# TFT_LCD_ER-TFT018-2.net
KiCad netlist of a schematic drawn in Altium Designer
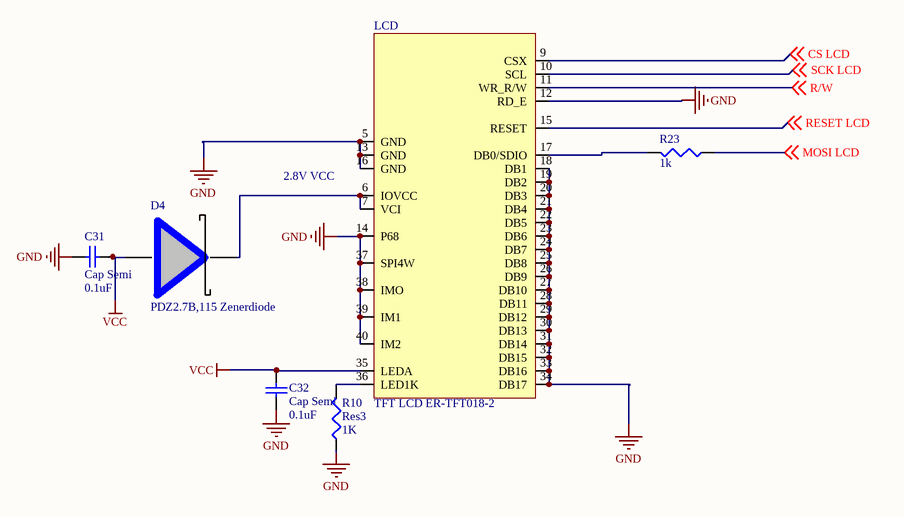
[diagram p0: TFT LCD ER-TFT018-2.SchDoc]

(export (version "E")
  (design (tool "Eeschema 10.0.6"))
  (components
    (comp (ref "C31")
      (value "Cap Semi")
      (footprint "1608[0603]")
      (description "Capacitor (Semiconductor SIM Model)")
      (fields (field (name "ALTIUM_VALUE") "0.1uF") (field (name "PUBLISHER") "Altium Limited"))
      (libsource (lib "Miscellaneous Devices") (part "Cap Semi"))
    )
    (comp (ref "C32")
      (value "Cap Semi")
      (footprint "1608[0603]")
      (description "Capacitor (Semiconductor SIM Model)")
      (fields (field (name "ALTIUM_VALUE") "0.1uF") (field (name "PUBLISHER") "Altium Limited"))
      (libsource (lib "Miscellaneous Devices") (part "Cap Semi"))
    )
    (comp (ref "D4")
      (value "PDZ2.7B,115 Zenerdiode")
      (footprint "PDZ2.7B,115")
      (libsource (lib "HGCDLibrary2") (part "PDZ2.7B,115 Zenerdiode"))
    )
    (comp (ref "LCD")
      (value "TFT LCD ER-TFT018-2")
      (footprint "LCD TFT Display")
      (libsource (lib "HGCDLibrary") (part "TFT LCD ER-TFT018-2"))
    )
    (comp (ref "R10")
      (value "Res3")
      (footprint "J1-0603")
      (description "Resistor")
      (fields (field (name "ALTIUM_VALUE") "1K") (field (name "PUBLISHER") "Altium Limited"))
      (libsource (lib "Miscellaneous Devices") (part "Res3"))
    )
    (comp (ref "R23")
      (value "1k")
      (footprint "J1-0603")
      (description "Resistor")
      (fields (field (name "Comment") "Res3") (field (name "PUBLISHER") "Altium Limited"))
      (libsource (lib "Miscellaneous Devices") (part "Res3"))
    )
  )
  (nets
    (net (code "1") (name "CS LCD") (class "Default")
      (node (ref "LCD") (pin "9") (pinfunction "CSX_9") (pintype "bidirectional"))
    )
    (net (code "2") (name "GND") (class "Default")
      (node (ref "C31") (pin "1") (pinfunction "1_1") (pintype "passive"))
      (node (ref "C32") (pin "1") (pinfunction "1_1") (pintype "passive"))
      (node (ref "LCD") (pin "12") (pinfunction "RD_E_12") (pintype "bidirectional"))
      (node (ref "LCD") (pin "13") (pinfunction "GND_13") (pintype "power_in"))
      (node (ref "LCD") (pin "14") (pinfunction "P68_14") (pintype "power_in"))
      (node (ref "LCD") (pin "16") (pinfunction "GND_16") (pintype "power_in"))
      (node (ref "LCD") (pin "18") (pinfunction "DB1_18") (pintype "bidirectional"))
      (node (ref "LCD") (pin "19") (pinfunction "DB2_19") (pintype "bidirectional"))
      (node (ref "LCD") (pin "20") (pinfunction "DB3_20") (pintype "bidirectional"))
      (node (ref "LCD") (pin "21") (pinfunction "DB4_21") (pintype "bidirectional"))
      (node (ref "LCD") (pin "22") (pinfunction "DB5_22") (pintype "bidirectional"))
      (node (ref "LCD") (pin "23") (pinfunction "DB6_23") (pintype "bidirectional"))
      (node (ref "LCD") (pin "24") (pinfunction "DB7_24") (pintype "bidirectional"))
      (node (ref "LCD") (pin "25") (pinfunction "DB8_25") (pintype "bidirectional"))
      (node (ref "LCD") (pin "26") (pinfunction "DB9_26") (pintype "bidirectional"))
      (node (ref "LCD") (pin "27") (pinfunction "DB10_27") (pintype "bidirectional"))
      (node (ref "LCD") (pin "28") (pinfunction "DB11_28") (pintype "bidirectional"))
      (node (ref "LCD") (pin "29") (pinfunction "DB12_29") (pintype "bidirectional"))
      (node (ref "LCD") (pin "30") (pinfunction "DB13_30") (pintype "bidirectional"))
      (node (ref "LCD") (pin "31") (pinfunction "DB14_31") (pintype "bidirectional"))
      (node (ref "LCD") (pin "32") (pinfunction "DB15_32") (pintype "bidirectional"))
      (node (ref "LCD") (pin "33") (pinfunction "DB16_33") (pintype "bidirectional"))
      (node (ref "LCD") (pin "34") (pinfunction "DB17_34") (pintype "bidirectional"))
      (node (ref "LCD") (pin "37") (pinfunction "SPI4W_37") (pintype "power_in"))
      (node (ref "LCD") (pin "38") (pinfunction "IMO_38") (pintype "power_in"))
      (node (ref "LCD") (pin "39") (pinfunction "IM1_39") (pintype "power_in"))
      (node (ref "LCD") (pin "40") (pinfunction "IM2_40") (pintype "power_in"))
      (node (ref "LCD") (pin "5") (pinfunction "GND_5") (pintype "power_in"))
      (node (ref "R10") (pin "1") (pinfunction "1_1") (pintype "passive"))
    )
    (net (code "3") (name "MOSI LCD") (class "Default")
      (node (ref "R23") (pin "1") (pinfunction "1_1") (pintype "passive"))
    )
    (net (code "4") (name "Net-(LCD-DB0{slash}SDIO)") (class "Default")
      (node (ref "LCD") (pin "17") (pinfunction "DB0/SDIO_17") (pintype "bidirectional"))
      (node (ref "R23") (pin "2") (pinfunction "2_2") (pintype "passive"))
    )
    (net (code "5") (name "Net-(LCD-IOVCC)") (class "Default")
      (node (ref "D4") (pin "1") (pinfunction "1_1") (pintype "passive"))
      (node (ref "LCD") (pin "6") (pinfunction "IOVCC_6") (pintype "power_in"))
      (node (ref "LCD") (pin "7") (pinfunction "VCI_7") (pintype "power_in"))
    )
    (net (code "6") (name "Net-(LCD-LED1K)") (class "Default")
      (node (ref "LCD") (pin "36") (pinfunction "LED1K_36") (pintype "power_in"))
      (node (ref "R10") (pin "2") (pinfunction "2_2") (pintype "passive"))
    )
    (net (code "7") (name "RESET LCD") (class "Default")
      (node (ref "LCD") (pin "15") (pinfunction "RESET_15") (pintype "bidirectional"))
    )
    (net (code "8") (name "R{slash}W") (class "Default")
      (node (ref "LCD") (pin "11") (pinfunction "WR_R/W_11") (pintype "bidirectional"))
    )
    (net (code "9") (name "SCK LCD") (class "Default")
      (node (ref "LCD") (pin "10") (pinfunction "SCL_10") (pintype "bidirectional"))
    )
    (net (code "10") (name "VCC") (class "Default")
      (node (ref "C31") (pin "2") (pinfunction "2_2") (pintype "passive"))
      (node (ref "C32") (pin "2") (pinfunction "2_2") (pintype "passive"))
      (node (ref "D4") (pin "2") (pinfunction "2_2") (pintype "passive"))
      (node (ref "LCD") (pin "35") (pinfunction "LEDA_35") (pintype "power_in"))
    )
  )
)
